# MAX9919.net
KiCad netlist of a schematic drawn in Altium Designer
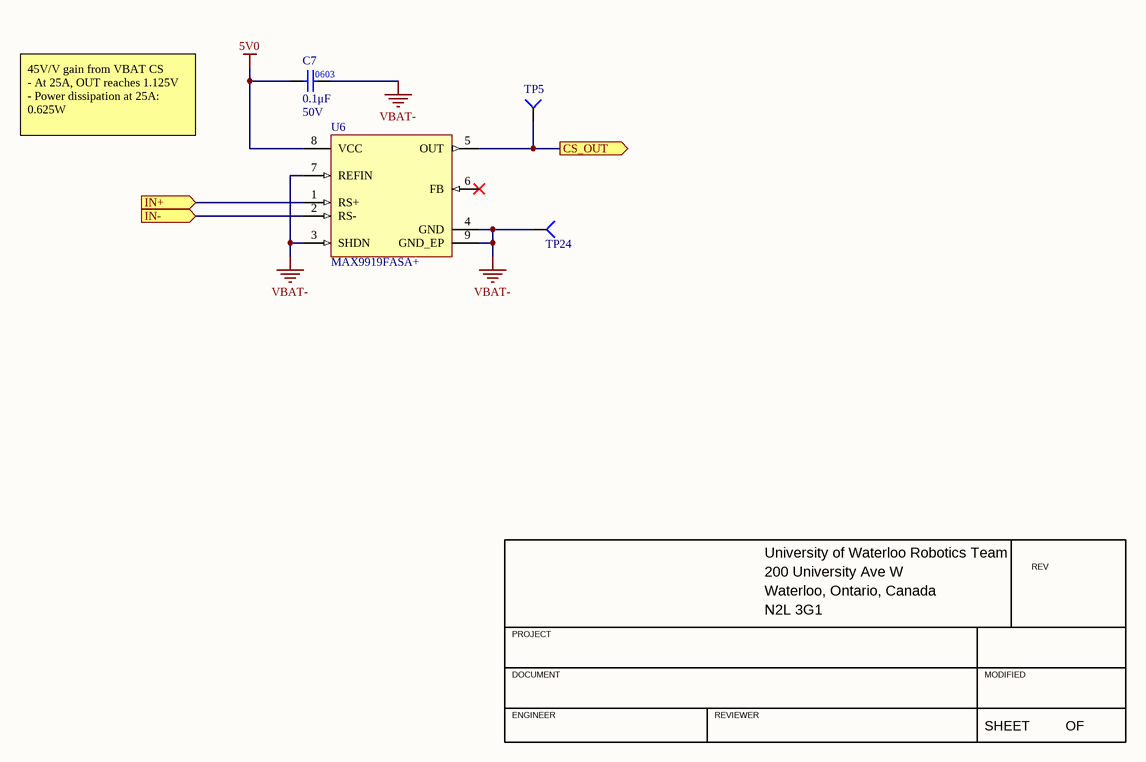
[diagram p0: MAX9919.SchDoc]

(export (version "E")
  (design (tool "Eeschema 10.0.6"))
  (components
    (comp (ref "C7")
      (value "0.1μF")
      (footprint "CAP0603")
      (description "CAP CER 0.1UF 50V X7R 0603")
      (fields (field (name "VOLTAGE RATING") "50V") (field (name "Comment") "CAP_0.1uF_50V_0603"))
      (libsource (lib "Personal_Schematic_Library_2022") (part "CAP_0.1uF_50V_0603"))
    )
    (comp (ref "TP5")
      (value "TESTPOINT_1MM_CIRCLE")
      (footprint "TESTPOINT_CIRCLE_1MM")
      (description "TESTPOINT 1MM CIRCLE")
      (libsource (lib "UWRT_Schematic_Library_2020") (part "TESTPOINT_1MM_CIRCLE"))
    )
    (comp (ref "TP24")
      (value "TESTPOINT_SMD_LOOP")
      (footprint "S1751-46R")
      (description "TESTPOINT SMD LOOP")
      (libsource (lib "UWRT_Schematic_Library_2020") (part "TESTPOINT_SMD_LOOP"))
    )
    (comp (ref "U6")
      (value "MAX9919FASA+")
      (footprint "8-SOIC_MAXIM_S8E+14")
      (description "IC CURRENT SENSE 1 CIRCUIT 8SOIC")
      (fields (field (name "MANUFACTURER PART NUMBER 1") "MAX9919FASA+"))
      (libsource (lib "Personal_Schematic_Library_2022") (part "MAX9919FASA+"))
    )
  )
  (nets
    (net (code "1") (name "/CS_OUT") (class "Default")
      (node (ref "TP5") (pin "1") (pinfunction "=value_1") (pintype "passive"))
      (node (ref "U6") (pin "5") (pinfunction "OUT_5") (pintype "output"))
    )
    (net (code "2") (name "/IN+") (class "Default")
      (node (ref "U6") (pin "1") (pinfunction "RS+_1") (pintype "input"))
    )
    (net (code "3") (name "/IN-") (class "Default")
      (node (ref "U6") (pin "2") (pinfunction "RS-_2") (pintype "input"))
    )
    (net (code "4") (name "5V0") (class "Default")
      (node (ref "C7") (pin "1") (pinfunction "1_1") (pintype "passive"))
      (node (ref "U6") (pin "8") (pinfunction "VCC_8") (pintype "power_in"))
    )
    (net (code "5") (name "VBAT-") (class "Default")
      (node (ref "C7") (pin "2") (pinfunction "2_2") (pintype "passive"))
      (node (ref "TP24") (pin "1") (pinfunction "=value_1") (pintype "passive"))
      (node (ref "U6") (pin "3") (pinfunction "SHDN_3") (pintype "input"))
      (node (ref "U6") (pin "4") (pinfunction "GND_4") (pintype "power_in"))
      (node (ref "U6") (pin "7") (pinfunction "REFIN_7") (pintype "input"))
      (node (ref "U6") (pin "9") (pinfunction "GND_EP_9") (pintype "power_in"))
    )
    (net (code "6") (name "unconnected-(U6-FB-Pad6)") (class "Default")
      (node (ref "U6") (pin "6") (pinfunction "FB_6") (pintype "input+no_connect"))
    )
  )
)
